# LDO.net
KiCad netlist of a schematic drawn in EAGLE
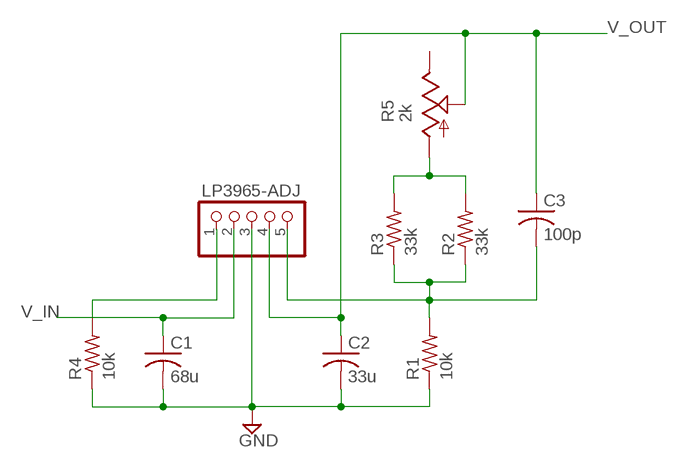
[diagram p0: schematic, sheet 1]

(export (version "E")
  (design (tool "Eeschema 10.0.6"))
  (components
    (comp (ref "C1")
      (value "68u")
      (footprint "eagle-import:C0805")
      (libsource (lib "eagle-import") (part "C-USC0805"))
    )
    (comp (ref "C2")
      (value "33u")
      (footprint "eagle-import:C0805")
      (libsource (lib "eagle-import") (part "C-USC0805"))
    )
    (comp (ref "C3")
      (value "100p")
      (footprint "eagle-import:C0805")
      (libsource (lib "eagle-import") (part "C-USC0805"))
    )
    (comp (ref "LP3965-ADJ")
      (value "PINHD-1X5")
      (footprint "eagle-import:1X05")
      (libsource (lib "eagle-import") (part "PINHD-1X5"))
    )
    (comp (ref "R1")
      (value "10k")
      (footprint "eagle-import:R0805")
      (libsource (lib "eagle-import") (part "R-US_R0805"))
    )
    (comp (ref "R2")
      (value "33k")
      (footprint "eagle-import:R0805")
      (libsource (lib "eagle-import") (part "R-US_R0805"))
    )
    (comp (ref "R3")
      (value "33k")
      (footprint "eagle-import:R0805")
      (libsource (lib "eagle-import") (part "R-US_R0805"))
    )
    (comp (ref "R4")
      (value "10k")
      (footprint "eagle-import:R0805")
      (libsource (lib "eagle-import") (part "R-US_R0805"))
    )
    (comp (ref "R5")
      (value "2k")
      (footprint "eagle-import:3223G")
      (libsource (lib "eagle-import") (part "TRIM_US-3223G"))
    )
  )
  (nets
    (net (code "1") (name "/V_IN") (class "Default")
      (node (ref "C1") (pin "1") (pinfunction "1_1") (pintype "passive"))
      (node (ref "LP3965-ADJ") (pin "2") (pinfunction "2_2") (pintype "passive"))
    )
    (net (code "2") (name "/V_OUT") (class "Default")
      (node (ref "C2") (pin "1") (pinfunction "1_1") (pintype "passive"))
      (node (ref "C3") (pin "1") (pinfunction "1_1") (pintype "passive"))
      (node (ref "LP3965-ADJ") (pin "4") (pinfunction "4_4") (pintype "passive"))
      (node (ref "R5") (pin "2") (pinfunction "S_2") (pintype "passive"))
    )
    (net (code "3") (name "GND") (class "Default")
      (node (ref "C1") (pin "2") (pinfunction "2_2") (pintype "passive"))
      (node (ref "C2") (pin "2") (pinfunction "2_2") (pintype "passive"))
      (node (ref "LP3965-ADJ") (pin "3") (pinfunction "3_3") (pintype "passive"))
      (node (ref "R1") (pin "1") (pinfunction "1_1") (pintype "passive"))
      (node (ref "R4") (pin "1") (pinfunction "1_1") (pintype "passive"))
    )
    (net (code "4") (name "Net-(C3-Pad2)") (class "Default")
      (node (ref "C3") (pin "2") (pinfunction "2_2") (pintype "passive"))
      (node (ref "LP3965-ADJ") (pin "5") (pinfunction "5_5") (pintype "passive"))
      (node (ref "R1") (pin "2") (pinfunction "2_2") (pintype "passive"))
      (node (ref "R2") (pin "1") (pinfunction "1_1") (pintype "passive"))
      (node (ref "R3") (pin "1") (pinfunction "1_1") (pintype "passive"))
    )
    (net (code "5") (name "Net-(LP3965-ADJ-Pad1)") (class "Default")
      (node (ref "LP3965-ADJ") (pin "1") (pinfunction "1_1") (pintype "passive"))
      (node (ref "R4") (pin "2") (pinfunction "2_2") (pintype "passive"))
    )
    (net (code "6") (name "Net-(R5-A)") (class "Default")
      (node (ref "R2") (pin "2") (pinfunction "2_2") (pintype "passive"))
      (node (ref "R3") (pin "2") (pinfunction "2_2") (pintype "passive"))
      (node (ref "R5") (pin "1") (pinfunction "A_1") (pintype "passive"))
    )
    (net (code "7") (name "unconnected-(R5-E-Pad3)") (class "Default")
      (node (ref "R5") (pin "3") (pinfunction "E_3") (pintype "passive"))
    )
  )
)
